# Copy_of_DAC_DifferenceAmp_jan30.net
KiCad netlist of a schematic drawn in Altium Designer
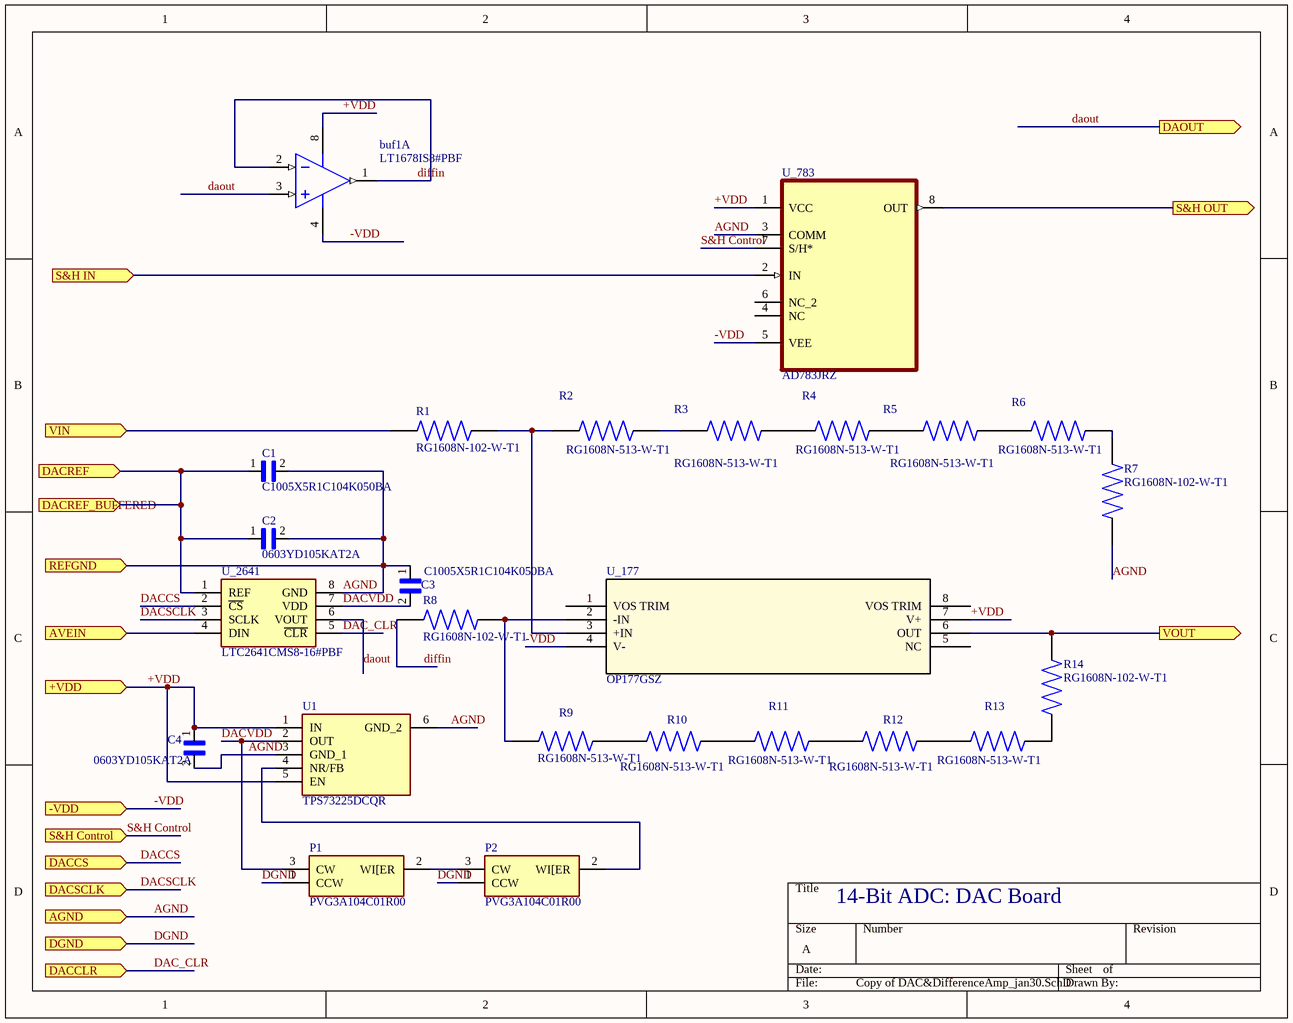
[diagram p0: Copy of DAC&DifferenceAmp_jan30.SchDoc]

(export (version "E")
  (design (tool "Eeschema 10.0.6"))
  (components
    (comp (ref "buf1")
      (value "LT1678IS8#PBF")
      (footprint "LT-S8-8_L")
      (fields
        (field (name "LINEAR TECHNOLOGY PART NUMBER") "LT1678")
        (field (name "MANUFACTURER") "Linear Technology")
      )
      (libsource (lib "Altium Content Vault") (part "LT-LT1678-S8-8"))
    )
    (comp (ref "C1")
      (value "C1005X5R1C104K050BA")
      (footprint "CAPC1005X55N")
      (description "CERAMIC CAPACITOR, 0.1UF, 16V, X5R, 10%, 0402")
      (libsource (lib "") (part "C1005X5R1C104K050BA_1"))
    )
    (comp (ref "C2")
      (value "0603YD105KAT2A")
      (footprint "CAPC1608X90N")
      (description "1ÂµF Â±10% 16V Ceramic Capacitor X5R 0603 (1608 Metric)")
      (fields (field (name "MF") "AVX"))
      (libsource (lib "") (part "0603YD105KAT2A_1"))
    )
    (comp (ref "C3")
      (value "C1005X5R1C104K050BA")
      (footprint "CAPC1005X55N")
      (description "CERAMIC CAPACITOR, 0.1UF, 16V, X5R, 10%, 0402")
      (libsource (lib "C1005X5R1C104K050BA") (part "C1005X5R1C104K050BA"))
    )
    (comp (ref "C4")
      (value "0603YD105KAT2A")
      (footprint "CAPC1608X90N")
      (description "1ÂµF Â±10% 16V Ceramic Capacitor X5R 0603 (1608 Metric)")
      (fields (field (name "MF") "AVX"))
      (libsource (lib "0603YD105KAT2A") (part "0603YD105KAT2A"))
    )
    (comp (ref "P1")
      (value "PVG3A104C01R00")
      (footprint "SamacSys:PVG3A104C01R00")
      (description "Variable Resistor")
      (fields (field (name "MOUSER2 PART NUMBER") "81-PVG3A104C01R00"))
      (libsource (lib "*") (part "PVG3A104C01R00"))
    )
    (comp (ref "P2")
      (value "PVG3A104C01R00")
      (footprint "SamacSys:PVG3A104C01R00")
      (description "Variable Resistor")
      (fields (field (name "MOUSER2 PART NUMBER") "81-PVG3A104C01R00"))
      (libsource (lib "*") (part "PVG3A104C01R00"))
    )
    (comp (ref "R1")
      (value "RG1608N-102-W-T1")
      (footprint "RESC1608X50N")
      (description "RES SMD 1K OHM 0.05% 1/10W 0603")
      (libsource (lib "RG1608N-102-W-T1") (part "RG1608N-102-W-T1"))
    )
    (comp (ref "R2")
      (value "RG1608N-513-W-T1")
      (footprint "RESC1608X50N")
      (libsource (lib "RG1608N-513-W-T1") (part "RG1608N-513-W-T1"))
    )
    (comp (ref "R3")
      (value "RG1608N-513-W-T1")
      (footprint "RESC1608X50N")
      (libsource (lib "RG1608N-513-W-T1") (part "RG1608N-513-W-T1"))
    )
    (comp (ref "R4")
      (value "RG1608N-513-W-T1")
      (footprint "RESC1608X50N")
      (libsource (lib "RG1608N-513-W-T1") (part "RG1608N-513-W-T1"))
    )
    (comp (ref "R5")
      (value "RG1608N-513-W-T1")
      (footprint "RESC1608X50N")
      (libsource (lib "RG1608N-513-W-T1") (part "RG1608N-513-W-T1"))
    )
    (comp (ref "R6")
      (value "RG1608N-513-W-T1")
      (footprint "RESC1608X50N")
      (libsource (lib "RG1608N-513-W-T1") (part "RG1608N-513-W-T1"))
    )
    (comp (ref "R7")
      (value "RG1608N-102-W-T1")
      (footprint "RESC1608X50N")
      (description "RES SMD 1K OHM 0.05% 1/10W 0603")
      (libsource (lib "RG1608N-102-W-T1") (part "RG1608N-102-W-T1"))
    )
    (comp (ref "R8")
      (value "RG1608N-102-W-T1")
      (footprint "RESC1608X50N")
      (description "RES SMD 1K OHM 0.05% 1/10W 0603")
      (libsource (lib "RG1608N-102-W-T1") (part "RG1608N-102-W-T1"))
    )
    (comp (ref "R9")
      (value "RG1608N-513-W-T1")
      (footprint "RESC1608X50N")
      (libsource (lib "RG1608N-513-W-T1") (part "RG1608N-513-W-T1"))
    )
    (comp (ref "R10")
      (value "RG1608N-513-W-T1")
      (footprint "RESC1608X50N")
      (libsource (lib "RG1608N-513-W-T1") (part "RG1608N-513-W-T1"))
    )
    (comp (ref "R11")
      (value "RG1608N-513-W-T1")
      (footprint "RESC1608X50N")
      (libsource (lib "RG1608N-513-W-T1") (part "RG1608N-513-W-T1"))
    )
    (comp (ref "R12")
      (value "RG1608N-513-W-T1")
      (footprint "RESC1608X50N")
      (libsource (lib "RG1608N-513-W-T1") (part "RG1608N-513-W-T1"))
    )
    (comp (ref "R13")
      (value "RG1608N-513-W-T1")
      (footprint "RESC1608X50N")
      (libsource (lib "RG1608N-513-W-T1") (part "RG1608N-513-W-T1"))
    )
    (comp (ref "R14")
      (value "RG1608N-102-W-T1")
      (footprint "RESC1608X50N")
      (description "RES SMD 1K OHM 0.05% 1/10W 0603")
      (libsource (lib "RG1608N-102-W-T1") (part "RG1608N-102-W-T1"))
    )
    (comp (ref "U1")
      (value "TPS73225DCQR")
      (footprint "SamacSys:SOT127P706X180-6N")
      (description "Integrated Circuit")
      (libsource (lib "*") (part "TPS73225DCQR"))
    )
    (comp (ref "U_177")
      (value "OP177GSZ")
      (footprint "R_8_ADI")
      (description "No Description Available")
      (fields (field (name "COPYRIGHT") "Copyright (C) 2021 Accelerated Designs. All rights reserved"))
      (libsource (lib "OP177GSZ") (part "OP177GSZ"))
    )
    (comp (ref "U_783")
      (value "AD783JRZ")
      (footprint "SOIC127P600X272-8N")
      (description "Sample and Hold Amplifier 1 Circuit 8-SOIC")
      (fields (field (name "MF") "Analog Devices"))
      (libsource (lib "AD783JRZ") (part "AD783JRZ"))
    )
    (comp (ref "U_2641")
      (value "LTC2641CMS8-16#PBF")
      (footprint "SamacSys:SOP65P490X110-8N")
      (description "Integrated Circuit")
      (fields (field (name "MOUSER PART NUMBER") "584-C2641CMS8-16PBF"))
      (libsource (lib "*") (part "LTC2641CMS8-16#PBF"))
    )
  )
  (nets
    (net (code "1") (name "/+VDD") (class "Default")
      (node (ref "C4") (pin "1") (pinfunction "1_1") (pintype "passive"))
      (node (ref "U1") (pin "1") (pinfunction "IN_1") (pintype "passive"))
      (node (ref "U1") (pin "5") (pinfunction "EN_5") (pintype "passive"))
      (node (ref "U_177") (pin "7") (pinfunction "V+_7") (pintype "power_in"))
      (node (ref "U_783") (pin "1") (pinfunction "VCC_1") (pintype "power_in"))
      (node (ref "buf1") (pin "8") (pinfunction "V+_8") (pintype "power_in"))
    )
    (net (code "2") (name "/-VDD") (class "Default")
      (node (ref "U_177") (pin "4") (pinfunction "V-_4") (pintype "power_in"))
      (node (ref "U_783") (pin "5") (pinfunction "VEE_5") (pintype "power_in"))
      (node (ref "buf1") (pin "4") (pinfunction "V-_4") (pintype "power_in"))
    )
    (net (code "3") (name "/AGND") (class "Default")
      (node (ref "C1") (pin "2") (pinfunction "2_2") (pintype "passive"))
      (node (ref "C2") (pin "2") (pinfunction "2_2") (pintype "passive"))
      (node (ref "C3") (pin "1") (pinfunction "1_1") (pintype "passive"))
      (node (ref "C4") (pin "2") (pinfunction "2_2") (pintype "passive"))
      (node (ref "R7") (pin "1") (pinfunction "1_1") (pintype "passive"))
      (node (ref "U1") (pin "3") (pinfunction "GND_1_3") (pintype "passive"))
      (node (ref "U1") (pin "6") (pinfunction "GND_2_6") (pintype "passive"))
      (node (ref "U_2641") (pin "8") (pinfunction "GND_8") (pintype "passive"))
      (node (ref "U_783") (pin "3") (pinfunction "COMM_3") (pintype "passive"))
    )
    (net (code "4") (name "/AVEIN") (class "Default")
      (node (ref "U_2641") (pin "4") (pinfunction "DIN_4") (pintype "passive"))
    )
    (net (code "5") (name "/DACCS") (class "Default")
      (node (ref "U_2641") (pin "2") (pinfunction "~{CS}_2") (pintype "passive"))
    )
    (net (code "6") (name "/DACREF") (class "Default")
      (node (ref "C1") (pin "1") (pinfunction "1_1") (pintype "passive"))
      (node (ref "C2") (pin "1") (pinfunction "1_1") (pintype "passive"))
      (node (ref "U_2641") (pin "1") (pinfunction "REF_1") (pintype "passive"))
    )
    (net (code "7") (name "/DACSCLK") (class "Default")
      (node (ref "U_2641") (pin "3") (pinfunction "SCLK_3") (pintype "passive"))
    )
    (net (code "8") (name "/DACVDD") (class "Default")
      (node (ref "C3") (pin "2") (pinfunction "2_2") (pintype "passive"))
      (node (ref "P1") (pin "3") (pinfunction "CW_3") (pintype "passive"))
      (node (ref "U1") (pin "2") (pinfunction "OUT_2") (pintype "passive"))
      (node (ref "U_2641") (pin "7") (pinfunction "VDD_7") (pintype "passive"))
    )
    (net (code "9") (name "/DAC_CLR") (class "Default")
      (node (ref "U_2641") (pin "5") (pinfunction "~{CLR}_5") (pintype "passive"))
    )
    (net (code "10") (name "/DGND") (class "Default")
      (node (ref "P1") (pin "1") (pinfunction "CCW_1") (pintype "passive"))
      (node (ref "P2") (pin "1") (pinfunction "CCW_1") (pintype "passive"))
    )
    (net (code "11") (name "/S&H Control") (class "Default")
      (node (ref "U_783") (pin "7") (pinfunction "S/H*_7") (pintype "passive"))
    )
    (net (code "12") (name "/S&H IN") (class "Default")
      (node (ref "U_783") (pin "2") (pinfunction "IN_2") (pintype "input"))
    )
    (net (code "13") (name "/S&H OUT") (class "Default")
      (node (ref "U_783") (pin "8") (pinfunction "OUT_8") (pintype "output"))
    )
    (net (code "14") (name "/VIN") (class "Default")
      (node (ref "R1") (pin "1") (pinfunction "1_1") (pintype "passive"))
    )
    (net (code "15") (name "/VOUT") (class "Default")
      (node (ref "R14") (pin "2") (pinfunction "2_2") (pintype "passive"))
      (node (ref "U_177") (pin "6") (pinfunction "OUT_6") (pintype "passive"))
    )
    (net (code "16") (name "/daout") (class "Default")
      (node (ref "U_2641") (pin "6") (pinfunction "VOUT_6") (pintype "passive"))
      (node (ref "buf1") (pin "3") (pinfunction "+IN_A_3") (pintype "input"))
    )
    (net (code "17") (name "/diffin") (class "Default")
      (node (ref "R8") (pin "1") (pinfunction "1_1") (pintype "passive"))
      (node (ref "buf1") (pin "1") (pinfunction "OUT_A_1") (pintype "output"))
      (node (ref "buf1") (pin "2") (pinfunction "-IN_A_2") (pintype "input"))
    )
    (net (code "18") (name "Net-(P1-WI[ER)") (class "Default")
      (node (ref "P1") (pin "2") (pinfunction "WI[ER_2") (pintype "passive"))
      (node (ref "P2") (pin "3") (pinfunction "CW_3") (pintype "passive"))
    )
    (net (code "19") (name "Net-(P2-WI[ER)") (class "Default")
      (node (ref "P2") (pin "2") (pinfunction "WI[ER_2") (pintype "passive"))
      (node (ref "U1") (pin "4") (pinfunction "NR/FB_4") (pintype "passive"))
    )
    (net (code "20") (name "Net-(R2-Pad2)") (class "Default")
      (node (ref "R2") (pin "2") (pinfunction "2_2") (pintype "passive"))
      (node (ref "R3") (pin "1") (pinfunction "1_1") (pintype "passive"))
    )
    (net (code "21") (name "Net-(R3-Pad2)") (class "Default")
      (node (ref "R3") (pin "2") (pinfunction "2_2") (pintype "passive"))
      (node (ref "R4") (pin "1") (pinfunction "1_1") (pintype "passive"))
    )
    (net (code "22") (name "Net-(R4-Pad2)") (class "Default")
      (node (ref "R4") (pin "2") (pinfunction "2_2") (pintype "passive"))
      (node (ref "R5") (pin "1") (pinfunction "1_1") (pintype "passive"))
    )
    (net (code "23") (name "Net-(R5-Pad2)") (class "Default")
      (node (ref "R5") (pin "2") (pinfunction "2_2") (pintype "passive"))
      (node (ref "R6") (pin "1") (pinfunction "1_1") (pintype "passive"))
    )
    (net (code "24") (name "Net-(R6-Pad2)") (class "Default")
      (node (ref "R6") (pin "2") (pinfunction "2_2") (pintype "passive"))
      (node (ref "R7") (pin "2") (pinfunction "2_2") (pintype "passive"))
    )
    (net (code "25") (name "Net-(R10-Pad1)") (class "Default")
      (node (ref "R10") (pin "1") (pinfunction "1_1") (pintype "passive"))
      (node (ref "R9") (pin "2") (pinfunction "2_2") (pintype "passive"))
    )
    (net (code "26") (name "Net-(R10-Pad2)") (class "Default")
      (node (ref "R10") (pin "2") (pinfunction "2_2") (pintype "passive"))
      (node (ref "R11") (pin "1") (pinfunction "1_1") (pintype "passive"))
    )
    (net (code "27") (name "Net-(R11-Pad2)") (class "Default")
      (node (ref "R11") (pin "2") (pinfunction "2_2") (pintype "passive"))
      (node (ref "R12") (pin "1") (pinfunction "1_1") (pintype "passive"))
    )
    (net (code "28") (name "Net-(R12-Pad2)") (class "Default")
      (node (ref "R12") (pin "2") (pinfunction "2_2") (pintype "passive"))
      (node (ref "R13") (pin "1") (pinfunction "1_1") (pintype "passive"))
    )
    (net (code "29") (name "Net-(R13-Pad2)") (class "Default")
      (node (ref "R13") (pin "2") (pinfunction "2_2") (pintype "passive"))
      (node (ref "R14") (pin "1") (pinfunction "1_1") (pintype "passive"))
    )
    (net (code "30") (name "Net-(U_177-+IN)") (class "Default")
      (node (ref "R1") (pin "2") (pinfunction "2_2") (pintype "passive"))
      (node (ref "R2") (pin "1") (pinfunction "1_1") (pintype "passive"))
      (node (ref "U_177") (pin "3") (pinfunction "+IN_3") (pintype "passive"))
    )
    (net (code "31") (name "Net-(U_177--IN)") (class "Default")
      (node (ref "R8") (pin "2") (pinfunction "2_2") (pintype "passive"))
      (node (ref "R9") (pin "1") (pinfunction "1_1") (pintype "passive"))
      (node (ref "U_177") (pin "2") (pinfunction "-IN_2") (pintype "passive"))
    )
    (net (code "32") (name "unconnected-(U_177-NC-Pad5)") (class "Default")
      (node (ref "U_177") (pin "5") (pinfunction "NC_5") (pintype "passive"))
    )
    (net (code "33") (name "unconnected-(U_177-VOS_TRIM-Pad1)") (class "Default")
      (node (ref "U_177") (pin "1") (pinfunction "VOS_TRIM_1") (pintype "passive"))
    )
    (net (code "34") (name "unconnected-(U_177-VOS_TRIM-Pad8)") (class "Default")
      (node (ref "U_177") (pin "8") (pinfunction "VOS_TRIM_8") (pintype "power_in"))
    )
    (net (code "35") (name "unconnected-(U_783-NC-Pad4)") (class "Default")
      (node (ref "U_783") (pin "4") (pinfunction "NC_4") (pintype "passive"))
    )
    (net (code "36") (name "unconnected-(U_783-NC_2-Pad6)") (class "Default")
      (node (ref "U_783") (pin "6") (pinfunction "NC_2_6") (pintype "passive"))
    )
  )
)
